# 1.net
KiCad netlist of a schematic drawn in EasyEDA Pro
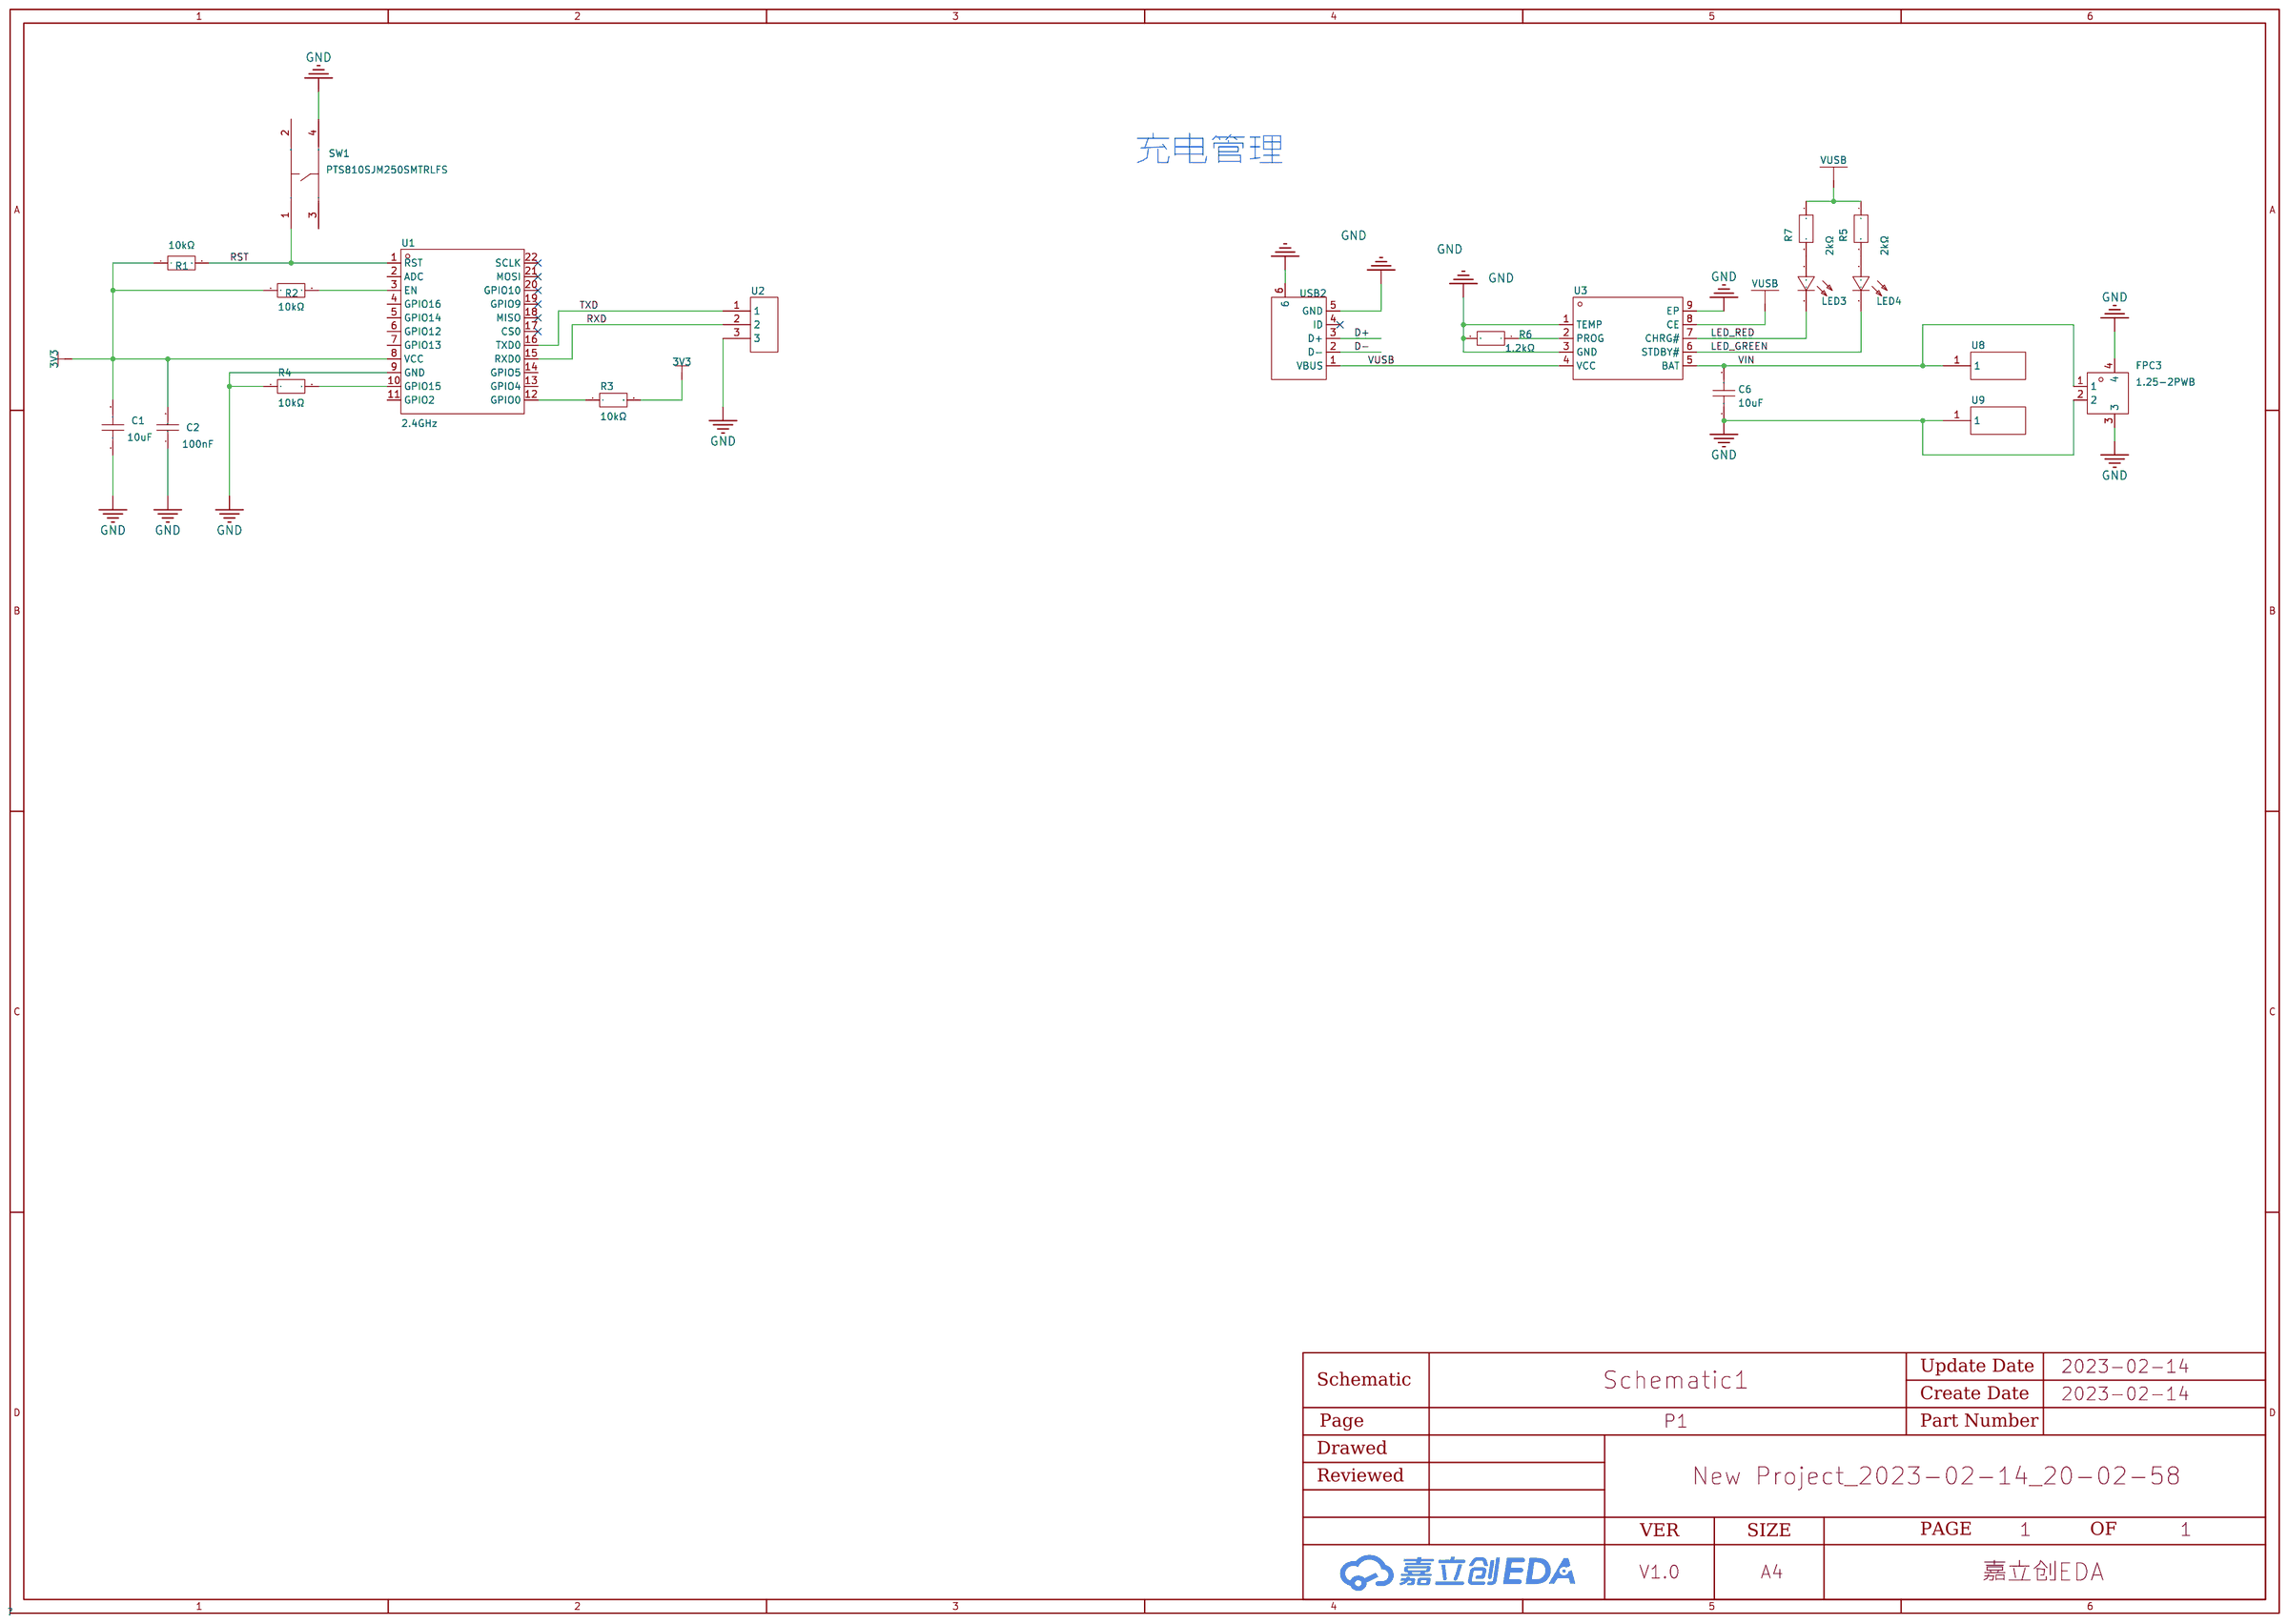
[diagram p0: schematic sheet]

(export (version "E")
  (design (tool "Eeschema 10.0.6"))
  (components
    (comp (ref "C1")
      (value "10uF")
      (footprint "easyedapro:C0805")
      (description "容值:10uF;精度:±10%;额定电压:50V;材质(温度系数):X5R;")
      (fields
        (field (name "Manufacturer Part") "CL21A106KBYQNNE")
        (field (name "Manufacturer") "SAMSUNG(三星)")
      )
      (libsource (lib "easyedapro") (part "CL21A106KBYQNNE"))
    )
    (comp (ref "C2")
      (value "100nF")
      (footprint "easyedapro:C0805")
      (description "容值:100nF;精度:±10%;额定电压:50V;材质(温度系数):X7R;")
      (fields
        (field (name "Manufacturer Part") "CL21B104KBCNNNC")
        (field (name "Manufacturer") "SAMSUNG(三星)")
      )
      (libsource (lib "easyedapro") (part "CL21B104KBCNNNC"))
    )
    (comp (ref "C6")
      (value "10uF")
      (footprint "easyedapro:C0603")
      (description "容值:10uF;精度:±20%;额定电压:25V;材质(温度系数):X5R;")
      (fields
        (field (name "Manufacturer Part") "CL10A106MA8NRNC")
        (field (name "Manufacturer") "SAMSUNG(三星)")
      )
      (libsource (lib "easyedapro") (part "CL10A106MA8NRNC"))
    )
    (comp (ref "FPC3")
      (value "1.25-2PWB")
      (footprint "easyedapro:CONN-SMD_2P-P1.25_DEALON_1.25-2PWB")
      (description "参考系列:-;间距:1.25mm;插针结构:1x2P;排数:1;每排PIN数:2;行距:-;公母:公型插针;安装方式:卧贴;额定电流:-;工作温度范围:-40~+85;")
      (fields (field (name "Manufacturer") "DEALON(德艺隆)"))
      (libsource (lib "easyedapro") (part "1.25-2PWB"))
    )
    (comp (ref "LED3")
      (value "~")
      (footprint "easyedapro:led0603-fd")
      (description "发光颜色:红灯;")
      (fields (field (name "Manufacturer Part") "NCD0603R1") (field (name "Manufacturer") "国星光电"))
      (libsource (lib "easyedapro") (part "fc-da1608hrk-620d"))
    )
    (comp (ref "LED4")
      (value "~")
      (footprint "easyedapro:led0603-fd")
      (description "发光颜色:红灯;")
      (fields (field (name "Manufacturer Part") "NCD0603R1") (field (name "Manufacturer") "国星光电"))
      (libsource (lib "easyedapro") (part "fc-da1608hrk-620d"))
    )
    (comp (ref "R1")
      (value "10kΩ")
      (footprint "easyedapro:R0805")
      (description "电阻类型:薄膜电阻;阻值:10kΩ;精度:±0.1%;功率:125mW;温度系数:±10ppm/°C;最大工作电压:100V;工作温度范围:-55°C~+155°C;")
      (fields (field (name "Manufacturer Part") "ERA6ARB103V") (field (name "Manufacturer") "PANASONIC(松下)"))
      (libsource (lib "easyedapro") (part "ERA6ARB103V"))
    )
    (comp (ref "R2")
      (value "10kΩ")
      (footprint "easyedapro:R0805")
      (description "电阻类型:薄膜电阻;阻值:10kΩ;精度:±0.1%;功率:125mW;温度系数:±10ppm/°C;最大工作电压:100V;工作温度范围:-55°C~+155°C;")
      (fields (field (name "Manufacturer Part") "ERA6ARB103V") (field (name "Manufacturer") "PANASONIC(松下)"))
      (libsource (lib "easyedapro") (part "ERA6ARB103V"))
    )
    (comp (ref "R3")
      (value "10kΩ")
      (footprint "easyedapro:R0805")
      (description "电阻类型:薄膜电阻;阻值:10kΩ;精度:±0.1%;功率:125mW;温度系数:±10ppm/°C;最大工作电压:100V;工作温度范围:-55°C~+155°C;")
      (fields (field (name "Manufacturer Part") "ERA6ARB103V") (field (name "Manufacturer") "PANASONIC(松下)"))
      (libsource (lib "easyedapro") (part "ERA6ARB103V"))
    )
    (comp (ref "R4")
      (value "10kΩ")
      (footprint "easyedapro:R0805")
      (description "电阻类型:薄膜电阻;阻值:10kΩ;精度:±0.1%;功率:125mW;温度系数:±10ppm/°C;最大工作电压:100V;工作温度范围:-55°C~+155°C;")
      (fields (field (name "Manufacturer Part") "ERA6ARB103V") (field (name "Manufacturer") "PANASONIC(松下)"))
      (libsource (lib "easyedapro") (part "ERA6ARB103V"))
    )
    (comp (ref "R5")
      (value "2kΩ")
      (footprint "easyedapro:r0603")
      (description "阻值:2kΩ;精度:±1%;功率:-;温度系数:-;")
      (fields (field (name "Manufacturer Part") "SG73P1JTTD1002F") (field (name "Manufacturer") "KOA"))
      (libsource (lib "easyedapro") (part "sg73p1jttd1002f"))
    )
    (comp (ref "R6")
      (value "1.2kΩ")
      (footprint "easyedapro:r0603")
      (description "阻值:10kΩ;精度:±1%;功率:-;温度系数:-;")
      (fields (field (name "Manufacturer Part") "SG73P1JTTD1002F") (field (name "Manufacturer") "KOA"))
      (libsource (lib "easyedapro") (part "sg73p1jttd1002f"))
    )
    (comp (ref "R7")
      (value "2kΩ")
      (footprint "easyedapro:r0603")
      (description "阻值:2kΩ;精度:±1%;功率:-;温度系数:-;")
      (fields (field (name "Manufacturer Part") "SG73P1JTTD1002F") (field (name "Manufacturer") "KOA"))
      (libsource (lib "easyedapro") (part "sg73p1jttd1002f"))
    )
    (comp (ref "SW1")
      (value "PTS810SJM250SMTRLFS")
      (footprint "easyedapro:KEY-SMD_4P-L4.2-W3.2-P2.20-LS4.6")
      (description "触点电流:50mA;额定电压(DC):16V;电路结构:单刀单掷;按钮作用方向:顶部触动;致动器样式:圆形按钮;照明颜色:-;开关长度:4.2mm;开关宽度:3.2mm;开关高度:2.5mm;")
      (fields (field (name "Manufacturer") "C&K"))
      (libsource (lib "easyedapro") (part "PTS810SJM250SMTRLFS"))
    )
    (comp (ref "U1")
      (value "2.4GHz")
      (footprint "easyedapro:WIFIM-SMD_ESP-12F-ESP8266MOD")
      (description "频率:2.4GHz;发射功率:16dBm;核心处理器:ESP8266;天线形式:PCB 板载天线;接收灵敏度:-90dBm;")
      (fields
        (field (name "Manufacturer Part") "ESP-12F(ESP8266MOD)")
        (field (name "Manufacturer") "Ai-Thinker(安信可)")
      )
      (libsource (lib "easyedapro") (part "ESP-12F(ESP8266MOD)"))
    )
    (comp (ref "U2") (value "~") (libsource (lib "easyedapro") (part "下载调试点")))
    (comp (ref "U3")
      (value "~")
      (footprint "easyedapro:ESOP-8_L4.9-W3.9-P1.27-LS6.0-BL-EP")
      (description "充电电池的类型:-;电池单元组数:-;最大充电电流:-;充满的电池组电压:-;最大供应电压:-;")
      (fields (field (name "Manufacturer Part") "TP4056") (field (name "Manufacturer") "UMW(友台半导体)"))
      (libsource (lib "easyedapro") (part "TP4056_C725790"))
    )
    (comp (ref "U8")
      (value "~")
      (footprint "easyedapro:电池焊接端子封装2")
      (libsource (lib "easyedapro") (part "电池焊接端子2"))
    )
    (comp (ref "U9")
      (value "~")
      (footprint "easyedapro:电池焊接端子封装2")
      (libsource (lib "easyedapro") (part "电池焊接端子2"))
    )
    (comp (ref "USB2")
      (value "~")
      (footprint "easyedapro:micro-usb-smd_u254-051n-4bh24-s2")
      (description "连接器类型:Micro-B;标准:USB 2.0;公母:母座;触点数量:5;端口数量:1;安装方式:卧贴;额定电流 - 电源:-;工作温度范围:-40~+85;")
      (fields
        (field (name "Manufacturer Part") "U254-051N-4BH24-S2S")
        (field (name "Manufacturer") "XKB Connectivity(中国星坤)")
      )
      (libsource (lib "easyedapro") (part "u254-051n-4bh24-s2s"))
    )
  )
  (nets
    (net (code "1") (name "/D+") (class "Default")
      (node (ref "USB2") (pin "3") (pinfunction "D+_3") (pintype "input"))
    )
    (net (code "2") (name "/D-") (class "Default")
      (node (ref "USB2") (pin "2") (pinfunction "D-_2") (pintype "input"))
    )
    (net (code "3") (name "/LED_GREEN") (class "Default")
      (node (ref "LED4") (pin "2") (pinfunction "K_2") (pintype "input"))
      (node (ref "U3") (pin "6") (pinfunction "STDBY#_6") (pintype "input"))
    )
    (net (code "4") (name "/LED_RED") (class "Default")
      (node (ref "LED3") (pin "2") (pinfunction "K_2") (pintype "input"))
      (node (ref "U3") (pin "7") (pinfunction "CHRG#_7") (pintype "input"))
    )
    (net (code "5") (name "/RST") (class "Default")
      (node (ref "R1") (pin "2") (pinfunction "2_2") (pintype "input"))
      (node (ref "SW1") (pin "1") (pinfunction "1_1") (pintype "input"))
      (node (ref "U1") (pin "1") (pinfunction "RST_1") (pintype "input"))
    )
    (net (code "6") (name "/RXD") (class "Default")
      (node (ref "U1") (pin "15") (pinfunction "RXD0_15") (pintype "input"))
      (node (ref "U2") (pin "2") (pinfunction "2_2") (pintype "input"))
    )
    (net (code "7") (name "/TXD") (class "Default")
      (node (ref "U1") (pin "16") (pinfunction "TXD0_16") (pintype "input"))
      (node (ref "U2") (pin "1") (pinfunction "1_1") (pintype "input"))
    )
    (net (code "8") (name "/VIN") (class "Default")
      (node (ref "C6") (pin "2") (pinfunction "2_2") (pintype "input"))
      (node (ref "FPC3") (pin "1") (pinfunction "1_1") (pintype "input"))
      (node (ref "U3") (pin "5") (pinfunction "BAT_5") (pintype "input"))
      (node (ref "U8") (pin "1") (pinfunction "1_1") (pintype "input"))
    )
    (net (code "9") (name "3V3") (class "Default")
      (node (ref "C1") (pin "2") (pinfunction "2_2") (pintype "input"))
      (node (ref "C2") (pin "2") (pinfunction "2_2") (pintype "input"))
      (node (ref "R1") (pin "1") (pinfunction "1_1") (pintype "input"))
      (node (ref "R2") (pin "1") (pinfunction "1_1") (pintype "input"))
      (node (ref "R3") (pin "2") (pinfunction "2_2") (pintype "input"))
      (node (ref "U1") (pin "8") (pinfunction "VCC_8") (pintype "input"))
    )
    (net (code "10") (name "GND") (class "Default")
      (node (ref "C1") (pin "1") (pinfunction "1_1") (pintype "input"))
      (node (ref "C2") (pin "1") (pinfunction "1_1") (pintype "input"))
      (node (ref "C6") (pin "1") (pinfunction "1_1") (pintype "input"))
      (node (ref "FPC3") (pin "2") (pinfunction "2_2") (pintype "input"))
      (node (ref "FPC3") (pin "3") (pinfunction "3_3") (pintype "input"))
      (node (ref "FPC3") (pin "4") (pinfunction "4_4") (pintype "input"))
      (node (ref "R4") (pin "1") (pinfunction "1_1") (pintype "input"))
      (node (ref "R6") (pin "2") (pinfunction "2_2") (pintype "input"))
      (node (ref "SW1") (pin "4") (pinfunction "4_4") (pintype "input"))
      (node (ref "U1") (pin "9") (pinfunction "GND_9") (pintype "input"))
      (node (ref "U2") (pin "3") (pinfunction "3_3") (pintype "input"))
      (node (ref "U3") (pin "1") (pinfunction "TEMP_1") (pintype "input"))
      (node (ref "U3") (pin "3") (pinfunction "GND_3") (pintype "input"))
      (node (ref "U3") (pin "9") (pinfunction "EP_9") (pintype "input"))
      (node (ref "U9") (pin "1") (pinfunction "1_1") (pintype "input"))
      (node (ref "USB2") (pin "5") (pinfunction "GND_5") (pintype "input"))
      (node (ref "USB2") (pin "6") (pinfunction "6_6") (pintype "input"))
    )
    (net (code "11") (name "Net-(LED3-A)") (class "Default")
      (node (ref "LED3") (pin "1") (pinfunction "A_1") (pintype "input"))
      (node (ref "R7") (pin "2") (pinfunction "2_2") (pintype "input"))
    )
    (net (code "12") (name "Net-(LED4-A)") (class "Default")
      (node (ref "LED4") (pin "1") (pinfunction "A_1") (pintype "input"))
      (node (ref "R5") (pin "2") (pinfunction "2_2") (pintype "input"))
    )
    (net (code "13") (name "Net-(U1-EN)") (class "Default")
      (node (ref "R2") (pin "2") (pinfunction "2_2") (pintype "input"))
      (node (ref "U1") (pin "3") (pinfunction "EN_3") (pintype "input"))
    )
    (net (code "14") (name "Net-(U1-GPIO0)") (class "Default")
      (node (ref "R3") (pin "1") (pinfunction "1_1") (pintype "input"))
      (node (ref "U1") (pin "12") (pinfunction "GPIO0_12") (pintype "input"))
    )
    (net (code "15") (name "Net-(U1-GPIO15)") (class "Default")
      (node (ref "R4") (pin "2") (pinfunction "2_2") (pintype "input"))
      (node (ref "U1") (pin "10") (pinfunction "GPIO15_10") (pintype "input"))
    )
    (net (code "16") (name "Net-(U3-PROG)") (class "Default")
      (node (ref "R6") (pin "1") (pinfunction "1_1") (pintype "input"))
      (node (ref "U3") (pin "2") (pinfunction "PROG_2") (pintype "input"))
    )
    (net (code "17") (name "VUSB") (class "Default")
      (node (ref "R5") (pin "1") (pinfunction "1_1") (pintype "input"))
      (node (ref "R7") (pin "1") (pinfunction "1_1") (pintype "input"))
      (node (ref "U3") (pin "4") (pinfunction "VCC_4") (pintype "input"))
      (node (ref "U3") (pin "8") (pinfunction "CE_8") (pintype "input"))
      (node (ref "USB2") (pin "1") (pinfunction "VBUS_1") (pintype "input"))
    )
    (net (code "18") (name "unconnected-(SW1-Pad2)") (class "Default")
      (node (ref "SW1") (pin "2") (pinfunction "2_2") (pintype "input"))
    )
    (net (code "19") (name "unconnected-(SW1-Pad3)") (class "Default")
      (node (ref "SW1") (pin "3") (pinfunction "3_3") (pintype "input"))
    )
    (net (code "20") (name "unconnected-(U1-ADC-Pad2)") (class "Default")
      (node (ref "U1") (pin "2") (pinfunction "ADC_2") (pintype "input"))
    )
    (net (code "21") (name "unconnected-(U1-CS0-Pad17)") (class "Default")
      (node (ref "U1") (pin "17") (pinfunction "CS0_17") (pintype "input+no_connect"))
    )
    (net (code "22") (name "unconnected-(U1-GPIO2-Pad11)") (class "Default")
      (node (ref "U1") (pin "11") (pinfunction "GPIO2_11") (pintype "input"))
    )
    (net (code "23") (name "unconnected-(U1-GPIO4-Pad13)") (class "Default")
      (node (ref "U1") (pin "13") (pinfunction "GPIO4_13") (pintype "input"))
    )
    (net (code "24") (name "unconnected-(U1-GPIO5-Pad14)") (class "Default")
      (node (ref "U1") (pin "14") (pinfunction "GPIO5_14") (pintype "input"))
    )
    (net (code "25") (name "unconnected-(U1-GPIO9-Pad19)") (class "Default")
      (node (ref "U1") (pin "19") (pinfunction "GPIO9_19") (pintype "input+no_connect"))
    )
    (net (code "26") (name "unconnected-(U1-GPIO10-Pad20)") (class "Default")
      (node (ref "U1") (pin "20") (pinfunction "GPIO10_20") (pintype "input+no_connect"))
    )
    (net (code "27") (name "unconnected-(U1-GPIO12-Pad6)") (class "Default")
      (node (ref "U1") (pin "6") (pinfunction "GPIO12_6") (pintype "input"))
    )
    (net (code "28") (name "unconnected-(U1-GPIO13-Pad7)") (class "Default")
      (node (ref "U1") (pin "7") (pinfunction "GPIO13_7") (pintype "input"))
    )
    (net (code "29") (name "unconnected-(U1-GPIO14-Pad5)") (class "Default")
      (node (ref "U1") (pin "5") (pinfunction "GPIO14_5") (pintype "input"))
    )
    (net (code "30") (name "unconnected-(U1-GPIO16-Pad4)") (class "Default")
      (node (ref "U1") (pin "4") (pinfunction "GPIO16_4") (pintype "input"))
    )
    (net (code "31") (name "unconnected-(U1-MISO-Pad18)") (class "Default")
      (node (ref "U1") (pin "18") (pinfunction "MISO_18") (pintype "input+no_connect"))
    )
    (net (code "32") (name "unconnected-(U1-MOSI-Pad21)") (class "Default")
      (node (ref "U1") (pin "21") (pinfunction "MOSI_21") (pintype "input+no_connect"))
    )
    (net (code "33") (name "unconnected-(U1-SCLK-Pad22)") (class "Default")
      (node (ref "U1") (pin "22") (pinfunction "SCLK_22") (pintype "input+no_connect"))
    )
    (net (code "34") (name "unconnected-(USB2-ID-Pad4)") (class "Default")
      (node (ref "USB2") (pin "4") (pinfunction "ID_4") (pintype "input+no_connect"))
    )
  )
)
